# vfd.net
KiCad netlist of a schematic drawn in EAGLE
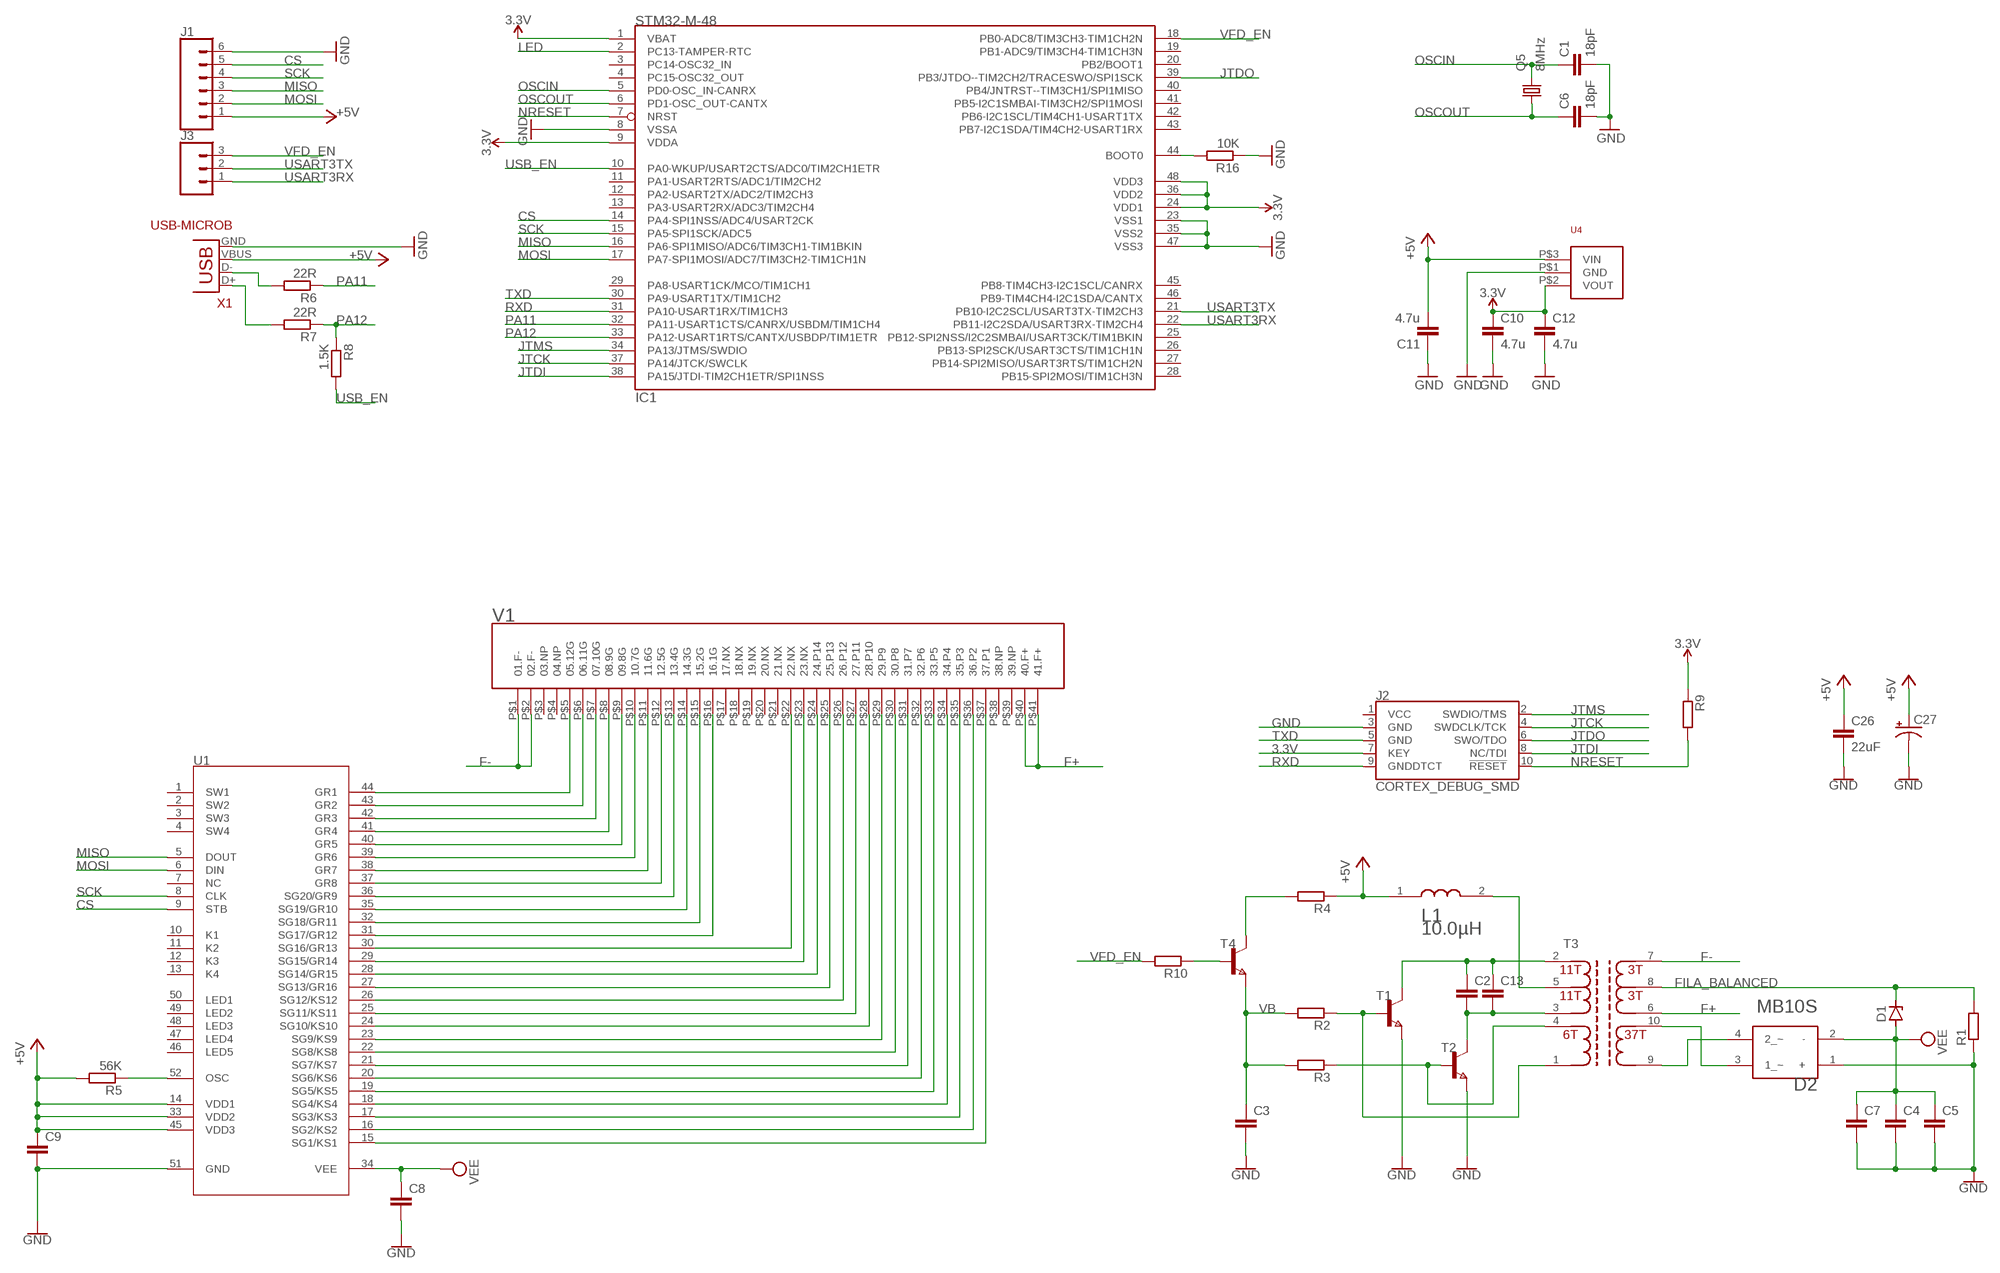
[diagram p0: schematic, sheet 1]

(export (version "E")
  (design (tool "Eeschema 10.0.6"))
  (components
    (comp (ref "C1")
      (value "18pF")
      (footprint "eagle-import:C0603")
      (libsource (lib "eagle-import") (part "resistor_348_C-EUC0603"))
    )
    (comp (ref "C2")
      (value "C-EUC1206")
      (footprint "eagle-import:C1206")
      (libsource (lib "eagle-import") (part "C-EUC1206"))
    )
    (comp (ref "C3")
      (value "C-EUC0805")
      (footprint "eagle-import:C0805")
      (libsource (lib "eagle-import") (part "C-EUC0805"))
    )
    (comp (ref "C4")
      (value "C-EUC0805")
      (footprint "eagle-import:C0805")
      (libsource (lib "eagle-import") (part "C-EUC0805"))
    )
    (comp (ref "C5")
      (value "C-EUC0805")
      (footprint "eagle-import:C0805")
      (libsource (lib "eagle-import") (part "C-EUC0805"))
    )
    (comp (ref "C6")
      (value "18pF")
      (footprint "eagle-import:C0603")
      (libsource (lib "eagle-import") (part "resistor_348_C-EUC0603"))
    )
    (comp (ref "C7")
      (value "C-EUC0805")
      (footprint "eagle-import:C0805")
      (libsource (lib "eagle-import") (part "C-EUC0805"))
    )
    (comp (ref "C8")
      (value "C-EUC0805")
      (footprint "eagle-import:C0805")
      (libsource (lib "eagle-import") (part "C-EUC0805"))
    )
    (comp (ref "C9")
      (value "C-EUC0805")
      (footprint "eagle-import:C0805")
      (libsource (lib "eagle-import") (part "C-EUC0805"))
    )
    (comp (ref "C10")
      (value "4.7u")
      (footprint "eagle-import:0805")
      (libsource (lib "eagle-import") (part "CAP0805"))
    )
    (comp (ref "C11")
      (value "4.7u")
      (footprint "eagle-import:0805")
      (libsource (lib "eagle-import") (part "CAP0805"))
    )
    (comp (ref "C12")
      (value "4.7u")
      (footprint "eagle-import:0805")
      (libsource (lib "eagle-import") (part "CAP0805"))
    )
    (comp (ref "C13")
      (value "C-EUC1206")
      (footprint "eagle-import:C1206")
      (libsource (lib "eagle-import") (part "C-EUC1206"))
    )
    (comp (ref "C26")
      (value "22uF")
      (footprint "eagle-import:C1206")
      (libsource (lib "eagle-import") (part "resistor_C-EUC1206"))
    )
    (comp (ref "C27")
      (value "CPOL-US153CLV-0807")
      (footprint "eagle-import:153CLV-0807")
      (libsource (lib "eagle-import") (part "CPOL-US153CLV-0807"))
    )
    (comp (ref "D1")
      (value "ZENER-DIODESOD80C")
      (footprint "eagle-import:SOD80C")
      (libsource (lib "eagle-import") (part "ZENER-DIODESOD80C"))
    )
    (comp (ref "D2")
      (value "ON_SEMI_MB10SON_SEMI_MB10S_0_0")
      (footprint "eagle-import:ON_SEMI_MB10S_0")
      (fields
        (field (name "DIGIKEY_PART_NUMBER") "MB10SCT-ND")
        (field (name "MF") "ON Semi")
        (field (name "MOUSER_PART_NUMBER") "512-MB10S")
      )
      (libsource (lib "eagle-import") (part "ON_SEMI_MB10SON_SEMI_MB10S_0_0"))
    )
    (comp (ref "IC1")
      (value "STM32-M-48")
      (footprint "eagle-import:LQFP48")
      (libsource (lib "eagle-import") (part "STM32-M-48"))
    )
    (comp (ref "J1")
      (value "CONN_06NO_SILK_FEMALE_PTH")
      (footprint "eagle-import:1X06_NO_SILK")
      (libsource (lib "eagle-import") (part "CONN_06NO_SILK_FEMALE_PTH"))
    )
    (comp (ref "J2")
      (value "CORTEX_DEBUG_SMD")
      (footprint "eagle-import:SAMTECH_FTSH-105-01")
      (libsource (lib "eagle-import") (part "CORTEX_DEBUG_SMD"))
    )
    (comp (ref "J3")
      (value "CONN_031X03_NO_SILK")
      (footprint "eagle-import:1X03_NO_SILK")
      (libsource (lib "eagle-import") (part "CONN_031X03_NO_SILK"))
    )
    (comp (ref "L1")
      (value "TDK_SLF7045T-100M1R3-PF")
      (footprint "eagle-import:ASWPA8050")
      (libsource (lib "eagle-import") (part "TDK_SLF7045T-100M1R3-PF"))
    )
    (comp (ref "Q5")
      (value "8MHz")
      (footprint "eagle-import:3.2X2.5_KX-7")
      (libsource (lib "eagle-import") (part "KX-7"))
    )
    (comp (ref "R1")
      (value "R-EU_R0603")
      (footprint "eagle-import:R0603")
      (libsource (lib "eagle-import") (part "R-EU_R0603"))
    )
    (comp (ref "R2")
      (value "R-EU_R0603")
      (footprint "eagle-import:R0603")
      (libsource (lib "eagle-import") (part "R-EU_R0603"))
    )
    (comp (ref "R3")
      (value "R-EU_R0603")
      (footprint "eagle-import:R0603")
      (libsource (lib "eagle-import") (part "R-EU_R0603"))
    )
    (comp (ref "R4")
      (value "R-EU_R0603")
      (footprint "eagle-import:R0603")
      (libsource (lib "eagle-import") (part "R-EU_R0603"))
    )
    (comp (ref "R5")
      (value "56K")
      (footprint "eagle-import:R0603")
      (libsource (lib "eagle-import") (part "R-EU_R0603"))
    )
    (comp (ref "R6")
      (value "22R")
      (footprint "eagle-import:R0603")
      (libsource (lib "eagle-import") (part "resistor_348_R-EU_R0603"))
    )
    (comp (ref "R7")
      (value "22R")
      (footprint "eagle-import:R0603")
      (libsource (lib "eagle-import") (part "resistor_348_R-EU_R0603"))
    )
    (comp (ref "R8")
      (value "1.5K")
      (footprint "eagle-import:R0603")
      (libsource (lib "eagle-import") (part "resistor_348_R-EU_R0603"))
    )
    (comp (ref "R9")
      (value "R-EU_R0603")
      (footprint "eagle-import:R0603")
      (libsource (lib "eagle-import") (part "R-EU_R0603"))
    )
    (comp (ref "R10")
      (value "R-EU_R0603")
      (footprint "eagle-import:R0603")
      (libsource (lib "eagle-import") (part "R-EU_R0603"))
    )
    (comp (ref "R16")
      (value "10K")
      (footprint "eagle-import:R0603")
      (libsource (lib "eagle-import") (part "resistor_348_R-EU_R0603"))
    )
    (comp (ref "T1")
      (value "NPNSOT23")
      (footprint "eagle-import:SOT-23")
      (fields (field (name "MPN") "DSS20201L-7"))
      (libsource (lib "eagle-import") (part "NPNSOT23"))
    )
    (comp (ref "T2")
      (value "NPNSOT23")
      (footprint "eagle-import:SOT-23")
      (fields (field (name "MPN") "DSS20201L-7"))
      (libsource (lib "eagle-import") (part "NPNSOT23"))
    )
    (comp (ref "T3")
      (value "TRANS_VFD_ER10P5")
      (footprint "eagle-import:ER10P5")
      (libsource (lib "eagle-import") (part "TRANS_VFD_ER10P5"))
    )
    (comp (ref "T4")
      (value "NPNSOT23")
      (footprint "eagle-import:SOT-23")
      (fields (field (name "MPN") "DSS20201L-7"))
      (libsource (lib "eagle-import") (part "NPNSOT23"))
    )
    (comp (ref "U1")
      (value "PT6311B")
      (footprint "eagle-import:QFP52_SOT379-1")
      (libsource (lib "eagle-import") (part "PT6311B"))
    )
    (comp (ref "U4")
      (value "MCP1703SOT-3.3V")
      (footprint "eagle-import:SOT-23A")
      (libsource (lib "eagle-import") (part "MCP1703SOT"))
    )
    (comp (ref "V1")
      (value "VFD_12SS62")
      (footprint "eagle-import:12SS62")
      (libsource (lib "eagle-import") (part "VFD_12SS62"))
    )
    (comp (ref "X1")
      (value "USB-MICROB")
      (footprint "eagle-import:USB-MICROB")
      (libsource (lib "eagle-import") (part "USB-MICROB"))
    )
  )
  (nets
    (net (code "1") (name "+5V") (class "Default")
      (node (ref "C11") (pin "2") (pinfunction "2_2") (pintype "passive"))
      (node (ref "C26") (pin "1") (pinfunction "1_1") (pintype "passive"))
      (node (ref "C27") (pin "+") (pinfunction "+_+") (pintype "passive"))
      (node (ref "C9") (pin "1") (pinfunction "1_1") (pintype "passive"))
      (node (ref "J1") (pin "1") (pinfunction "1_1") (pintype "passive"))
      (node (ref "L1") (pin "1") (pinfunction "1_1") (pintype "bidirectional"))
      (node (ref "R4") (pin "1") (pinfunction "1_1") (pintype "passive"))
      (node (ref "R5") (pin "2") (pinfunction "2_2") (pintype "passive"))
      (node (ref "U1") (pin "14") (pinfunction "VDD1_14") (pintype "bidirectional"))
      (node (ref "U1") (pin "33") (pinfunction "VDD2_33") (pintype "bidirectional"))
      (node (ref "U1") (pin "45") (pinfunction "VDD3_45") (pintype "bidirectional"))
      (node (ref "U4") (pin "P$3") (pinfunction "VIN_P$3") (pintype "bidirectional"))
      (node (ref "X1") (pin "VBUS") (pinfunction "VBUS_VBUS") (pintype "bidirectional"))
    )
    (net (code "2") (name "/CS") (class "Default")
      (node (ref "IC1") (pin "14") (pinfunction "PA4-SPI1NSS/ADC4/USART2CK_14") (pintype "bidirectional"))
      (node (ref "J1") (pin "5") (pinfunction "5_5") (pintype "passive"))
      (node (ref "U1") (pin "9") (pinfunction "STB_9") (pintype "bidirectional"))
    )
    (net (code "3") (name "/F+") (class "Default")
      (node (ref "T3") (pin "6") (pinfunction "6_6") (pintype "bidirectional"))
      (node (ref "V1") (pin "P$40") (pinfunction "40.F+_P$40") (pintype "bidirectional"))
      (node (ref "V1") (pin "P$41") (pinfunction "41.F+_P$41") (pintype "bidirectional"))
    )
    (net (code "4") (name "/F-") (class "Default")
      (node (ref "T3") (pin "7") (pinfunction "7_7") (pintype "bidirectional"))
      (node (ref "V1") (pin "P$1") (pinfunction "01.F-_P$1") (pintype "bidirectional"))
      (node (ref "V1") (pin "P$2") (pinfunction "02.F-_P$2") (pintype "bidirectional"))
    )
    (net (code "5") (name "/FILA_BALANCED") (class "Default")
      (node (ref "D1") (pin "C") (pinfunction "C_C") (pintype "passive"))
      (node (ref "R1") (pin "2") (pinfunction "2_2") (pintype "passive"))
      (node (ref "T3") (pin "8") (pinfunction "8_8") (pintype "bidirectional"))
    )
    (net (code "6") (name "/JTCK") (class "Default")
      (node (ref "IC1") (pin "37") (pinfunction "PA14/JTCK/SWCLK_37") (pintype "bidirectional"))
      (node (ref "J2") (pin "4") (pinfunction "SWDCLK/TCK_4") (pintype "bidirectional"))
    )
    (net (code "7") (name "/JTDI") (class "Default")
      (node (ref "IC1") (pin "38") (pinfunction "PA15/JTDI-TIM2CH1ETR/SPI1NSS_38") (pintype "bidirectional"))
      (node (ref "J2") (pin "8") (pinfunction "NC/TDI_8") (pintype "bidirectional"))
    )
    (net (code "8") (name "/JTDO") (class "Default")
      (node (ref "IC1") (pin "39") (pinfunction "PB3/JTDO--TIM2CH2/TRACESWO/SPI1SCK_39") (pintype "bidirectional"))
      (node (ref "J2") (pin "6") (pinfunction "SWO/TDO_6") (pintype "bidirectional"))
    )
    (net (code "9") (name "/JTMS") (class "Default")
      (node (ref "IC1") (pin "34") (pinfunction "PA13/JTMS/SWDIO_34") (pintype "bidirectional"))
      (node (ref "J2") (pin "2") (pinfunction "SWDIO/TMS_2") (pintype "bidirectional"))
    )
    (net (code "10") (name "/LED") (class "Default")
      (node (ref "IC1") (pin "2") (pinfunction "PC13-TAMPER-RTC_2") (pintype "bidirectional"))
    )
    (net (code "11") (name "/MISO") (class "Default")
      (node (ref "IC1") (pin "16") (pinfunction "PA6-SPI1MISO/ADC6/TIM3CH1-TIM1BKIN_16") (pintype "bidirectional"))
      (node (ref "J1") (pin "3") (pinfunction "3_3") (pintype "passive"))
      (node (ref "U1") (pin "5") (pinfunction "DOUT_5") (pintype "bidirectional"))
    )
    (net (code "12") (name "/MOSI") (class "Default")
      (node (ref "IC1") (pin "17") (pinfunction "PA7-SPI1MOSI/ADC7/TIM3CH2-TIM1CH1N_17") (pintype "bidirectional"))
      (node (ref "J1") (pin "2") (pinfunction "2_2") (pintype "passive"))
      (node (ref "U1") (pin "6") (pinfunction "DIN_6") (pintype "bidirectional"))
    )
    (net (code "13") (name "/NRESET") (class "Default")
      (node (ref "IC1") (pin "7") (pinfunction "NRST_7") (pintype "bidirectional"))
      (node (ref "J2") (pin "10") (pinfunction "~{RESET}_10") (pintype "bidirectional"))
      (node (ref "R9") (pin "2") (pinfunction "2_2") (pintype "passive"))
    )
    (net (code "14") (name "/OSCIN") (class "Default")
      (node (ref "C1") (pin "1") (pinfunction "1_1") (pintype "passive"))
      (node (ref "IC1") (pin "5") (pinfunction "PD0-OSC_IN-CANRX_5") (pintype "input"))
      (node (ref "Q5") (pin "3") (pinfunction "2_3") (pintype "passive"))
    )
    (net (code "15") (name "/OSCOUT") (class "Default")
      (node (ref "C6") (pin "1") (pinfunction "1_1") (pintype "passive"))
      (node (ref "IC1") (pin "6") (pinfunction "PD1-OSC_OUT-CANTX_6") (pintype "output"))
      (node (ref "Q5") (pin "1") (pinfunction "1_1") (pintype "passive"))
    )
    (net (code "16") (name "/PA11") (class "Default")
      (node (ref "IC1") (pin "32") (pinfunction "PA11-USART1CTS/CANRX/USBDM/TIM1CH4_32") (pintype "bidirectional"))
      (node (ref "R6") (pin "1") (pinfunction "1_1") (pintype "passive"))
    )
    (net (code "17") (name "/PA12") (class "Default")
      (node (ref "IC1") (pin "33") (pinfunction "PA12-USART1RTS/CANTX/USBDP/TIM1ETR_33") (pintype "bidirectional"))
      (node (ref "R7") (pin "1") (pinfunction "1_1") (pintype "passive"))
      (node (ref "R8") (pin "1") (pinfunction "1_1") (pintype "passive"))
    )
    (net (code "18") (name "/RXD") (class "Default")
      (node (ref "IC1") (pin "31") (pinfunction "PA10-USART1RX/TIM1CH3_31") (pintype "bidirectional"))
      (node (ref "J2") (pin "9") (pinfunction "GNDDTCT_9") (pintype "bidirectional"))
    )
    (net (code "19") (name "/SCK") (class "Default")
      (node (ref "IC1") (pin "15") (pinfunction "PA5-SPI1SCK/ADC5_15") (pintype "bidirectional"))
      (node (ref "J1") (pin "4") (pinfunction "4_4") (pintype "passive"))
      (node (ref "U1") (pin "8") (pinfunction "CLK_8") (pintype "bidirectional"))
    )
    (net (code "20") (name "/TXD") (class "Default")
      (node (ref "IC1") (pin "30") (pinfunction "PA9-USART1TX/TIM1CH2_30") (pintype "bidirectional"))
      (node (ref "J2") (pin "5") (pinfunction "GND_5") (pintype "bidirectional"))
    )
    (net (code "21") (name "/USART3RX") (class "Default")
      (node (ref "IC1") (pin "22") (pinfunction "PB11-I2C2SDA/USART3RX-TIM2CH4_22") (pintype "bidirectional"))
      (node (ref "J3") (pin "1") (pinfunction "1_1") (pintype "passive"))
    )
    (net (code "22") (name "/USART3TX") (class "Default")
      (node (ref "IC1") (pin "21") (pinfunction "PB10-I2C2SCL/USART3TX-TIM2CH3_21") (pintype "bidirectional"))
      (node (ref "J3") (pin "2") (pinfunction "2_2") (pintype "passive"))
    )
    (net (code "23") (name "/USB_EN") (class "Default")
      (node (ref "IC1") (pin "10") (pinfunction "PA0-WKUP/USART2CTS/ADC0/TIM2CH1ETR_10") (pintype "bidirectional"))
      (node (ref "R8") (pin "2") (pinfunction "2_2") (pintype "passive"))
    )
    (net (code "24") (name "/VB") (class "Default")
      (node (ref "C3") (pin "1") (pinfunction "1_1") (pintype "passive"))
      (node (ref "R2") (pin "2") (pinfunction "2_2") (pintype "passive"))
      (node (ref "R3") (pin "2") (pinfunction "2_2") (pintype "passive"))
      (node (ref "T4") (pin "2") (pinfunction "E_2") (pintype "passive"))
    )
    (net (code "25") (name "/VFD_EN") (class "Default")
      (node (ref "IC1") (pin "18") (pinfunction "PB0-ADC8/TIM3CH3-TIM1CH2N_18") (pintype "bidirectional"))
      (node (ref "J3") (pin "3") (pinfunction "3_3") (pintype "passive"))
      (node (ref "R10") (pin "2") (pinfunction "2_2") (pintype "passive"))
    )
    (net (code "26") (name "3.3V") (class "Default")
      (node (ref "C10") (pin "1") (pinfunction "1_1") (pintype "passive"))
      (node (ref "C12") (pin "1") (pinfunction "1_1") (pintype "passive"))
      (node (ref "IC1") (pin "1") (pinfunction "VBAT_1") (pintype "power_in"))
      (node (ref "IC1") (pin "24") (pinfunction "VDD1_24") (pintype "power_in"))
      (node (ref "IC1") (pin "36") (pinfunction "VDD2_36") (pintype "power_in"))
      (node (ref "IC1") (pin "48") (pinfunction "VDD3_48") (pintype "power_in"))
      (node (ref "IC1") (pin "9") (pinfunction "VDDA_9") (pintype "power_in"))
      (node (ref "J2") (pin "7") (pinfunction "KEY_7") (pintype "bidirectional"))
      (node (ref "R9") (pin "1") (pinfunction "1_1") (pintype "passive"))
      (node (ref "U4") (pin "P$2") (pinfunction "VOUT_P$2") (pintype "bidirectional"))
    )
    (net (code "27") (name "GND") (class "Default")
      (node (ref "C1") (pin "2") (pinfunction "2_2") (pintype "passive"))
      (node (ref "C10") (pin "2") (pinfunction "2_2") (pintype "passive"))
      (node (ref "C11") (pin "1") (pinfunction "1_1") (pintype "passive"))
      (node (ref "C12") (pin "2") (pinfunction "2_2") (pintype "passive"))
      (node (ref "C26") (pin "2") (pinfunction "2_2") (pintype "passive"))
      (node (ref "C27") (pin "-") (pinfunction "-_-") (pintype "passive"))
      (node (ref "C3") (pin "2") (pinfunction "2_2") (pintype "passive"))
      (node (ref "C4") (pin "2") (pinfunction "2_2") (pintype "passive"))
      (node (ref "C5") (pin "2") (pinfunction "2_2") (pintype "passive"))
      (node (ref "C6") (pin "2") (pinfunction "2_2") (pintype "passive"))
      (node (ref "C7") (pin "2") (pinfunction "2_2") (pintype "passive"))
      (node (ref "C8") (pin "2") (pinfunction "2_2") (pintype "passive"))
      (node (ref "C9") (pin "2") (pinfunction "2_2") (pintype "passive"))
      (node (ref "D2") (pin "1") (pinfunction "+_1") (pintype "passive"))
      (node (ref "IC1") (pin "23") (pinfunction "VSS1_23") (pintype "power_in"))
      (node (ref "IC1") (pin "35") (pinfunction "VSS2_35") (pintype "power_in"))
      (node (ref "IC1") (pin "47") (pinfunction "VSS3_47") (pintype "power_in"))
      (node (ref "IC1") (pin "8") (pinfunction "VSSA_8") (pintype "power_in"))
      (node (ref "J1") (pin "6") (pinfunction "6_6") (pintype "passive"))
      (node (ref "J2") (pin "3") (pinfunction "GND_3") (pintype "bidirectional"))
      (node (ref "R1") (pin "1") (pinfunction "1_1") (pintype "passive"))
      (node (ref "R16") (pin "1") (pinfunction "1_1") (pintype "passive"))
      (node (ref "T1") (pin "2") (pinfunction "E_2") (pintype "passive"))
      (node (ref "T2") (pin "2") (pinfunction "E_2") (pintype "passive"))
      (node (ref "U1") (pin "51") (pinfunction "GND_51") (pintype "bidirectional"))
      (node (ref "U4") (pin "P$1") (pinfunction "GND_P$1") (pintype "bidirectional"))
      (node (ref "X1") (pin "GND") (pinfunction "GND_GND") (pintype "bidirectional"))
    )
    (net (code "28") (name "Net-(D2-1_~{})") (class "Default")
      (node (ref "D2") (pin "3") (pinfunction "1_~{}_3") (pintype "passive"))
      (node (ref "T3") (pin "10") (pinfunction "10_10") (pintype "bidirectional"))
    )
    (net (code "29") (name "Net-(D2-2_~{})") (class "Default")
      (node (ref "D2") (pin "4") (pinfunction "2_~{}_4") (pintype "passive"))
      (node (ref "T3") (pin "9") (pinfunction "9_9") (pintype "bidirectional"))
    )
    (net (code "30") (name "Net-(IC1-BOOT0)") (class "Default")
      (node (ref "IC1") (pin "44") (pinfunction "BOOT0_44") (pintype "input"))
      (node (ref "R16") (pin "2") (pinfunction "2_2") (pintype "passive"))
    )
    (net (code "31") (name "Net-(L1-Pad2)") (class "Default")
      (node (ref "L1") (pin "2") (pinfunction "2_2") (pintype "bidirectional"))
      (node (ref "T3") (pin "5") (pinfunction "5_5") (pintype "bidirectional"))
    )
    (net (code "32") (name "Net-(R6-Pad2)") (class "Default")
      (node (ref "R6") (pin "2") (pinfunction "2_2") (pintype "passive"))
      (node (ref "X1") (pin "D-") (pinfunction "D-_D-") (pintype "bidirectional"))
    )
    (net (code "33") (name "Net-(R7-Pad2)") (class "Default")
      (node (ref "R7") (pin "2") (pinfunction "2_2") (pintype "passive"))
      (node (ref "X1") (pin "D+") (pinfunction "D+_D+") (pintype "bidirectional"))
    )
    (net (code "34") (name "Net-(T1-B)") (class "Default")
      (node (ref "R2") (pin "1") (pinfunction "1_1") (pintype "passive"))
      (node (ref "T1") (pin "3") (pinfunction "B_3") (pintype "passive"))
      (node (ref "T3") (pin "1") (pinfunction "1_1") (pintype "bidirectional"))
    )
    (net (code "35") (name "Net-(T1-C)") (class "Default")
      (node (ref "C13") (pin "1") (pinfunction "1_1") (pintype "passive"))
      (node (ref "C2") (pin "1") (pinfunction "1_1") (pintype "passive"))
      (node (ref "T1") (pin "1") (pinfunction "C_1") (pintype "passive"))
      (node (ref "T3") (pin "2") (pinfunction "2_2") (pintype "bidirectional"))
    )
    (net (code "36") (name "Net-(T2-B)") (class "Default")
      (node (ref "R3") (pin "1") (pinfunction "1_1") (pintype "passive"))
      (node (ref "T2") (pin "3") (pinfunction "B_3") (pintype "passive"))
      (node (ref "T3") (pin "4") (pinfunction "4_4") (pintype "bidirectional"))
    )
    (net (code "37") (name "Net-(T2-C)") (class "Default")
      (node (ref "C13") (pin "2") (pinfunction "2_2") (pintype "passive"))
      (node (ref "C2") (pin "2") (pinfunction "2_2") (pintype "passive"))
      (node (ref "T2") (pin "1") (pinfunction "C_1") (pintype "passive"))
      (node (ref "T3") (pin "3") (pinfunction "3_3") (pintype "bidirectional"))
    )
    (net (code "38") (name "Net-(T4-B)") (class "Default")
      (node (ref "R10") (pin "1") (pinfunction "1_1") (pintype "passive"))
      (node (ref "T4") (pin "3") (pinfunction "B_3") (pintype "passive"))
    )
    (net (code "39") (name "Net-(T4-C)") (class "Default")
      (node (ref "R4") (pin "2") (pinfunction "2_2") (pintype "passive"))
      (node (ref "T4") (pin "1") (pinfunction "C_1") (pintype "passive"))
    )
    (net (code "40") (name "Net-(U1-GR1)") (class "Default")
      (node (ref "U1") (pin "44") (pinfunction "GR1_44") (pintype "bidirectional"))
      (node (ref "V1") (pin "P$5") (pinfunction "05.12G_P$5") (pintype "bidirectional"))
    )
    (net (code "41") (name "Net-(U1-GR2)") (class "Default")
      (node (ref "U1") (pin "43") (pinfunction "GR2_43") (pintype "bidirectional"))
      (node (ref "V1") (pin "P$6") (pinfunction "06.11G_P$6") (pintype "bidirectional"))
    )
    (net (code "42") (name "Net-(U1-GR3)") (class "Default")
      (node (ref "U1") (pin "42") (pinfunction "GR3_42") (pintype "bidirectional"))
      (node (ref "V1") (pin "P$7") (pinfunction "07.10G_P$7") (pintype "bidirectional"))
    )
    (net (code "43") (name "Net-(U1-GR4)") (class "Default")
      (node (ref "U1") (pin "41") (pinfunction "GR4_41") (pintype "bidirectional"))
      (node (ref "V1") (pin "P$8") (pinfunction "08.9G_P$8") (pintype "bidirectional"))
    )
    (net (code "44") (name "Net-(U1-GR5)") (class "Default")
      (node (ref "U1") (pin "40") (pinfunction "GR5_40") (pintype "bidirectional"))
      (node (ref "V1") (pin "P$9") (pinfunction "09.8G_P$9") (pintype "bidirectional"))
    )
    (net (code "45") (name "Net-(U1-GR6)") (class "Default")
      (node (ref "U1") (pin "39") (pinfunction "GR6_39") (pintype "bidirectional"))
      (node (ref "V1") (pin "P$10") (pinfunction "10.7G_P$10") (pintype "bidirectional"))
    )
    (net (code "46") (name "Net-(U1-GR7)") (class "Default")
      (node (ref "U1") (pin "38") (pinfunction "GR7_38") (pintype "bidirectional"))
      (node (ref "V1") (pin "P$11") (pinfunction "11.6G_P$11") (pintype "bidirectional"))
    )
    (net (code "47") (name "Net-(U1-GR8)") (class "Default")
      (node (ref "U1") (pin "37") (pinfunction "GR8_37") (pintype "bidirectional"))
      (node (ref "V1") (pin "P$12") (pinfunction "12.5G_P$12") (pintype "bidirectional"))
    )
    (net (code "48") (name "Net-(U1-OSC)") (class "Default")
      (node (ref "R5") (pin "1") (pinfunction "1_1") (pintype "passive"))
      (node (ref "U1") (pin "52") (pinfunction "OSC_52") (pintype "bidirectional"))
    )
    (net (code "49") (name "Net-(U1-SG1{slash}KS1)") (class "Default")
      (node (ref "U1") (pin "15") (pinfunction "SG1/KS1_15") (pintype "bidirectional"))
      (node (ref "V1") (pin "P$37") (pinfunction "37.P1_P$37") (pintype "bidirectional"))
    )
    (net (code "50") (name "Net-(U1-SG2{slash}KS2)") (class "Default")
      (node (ref "U1") (pin "16") (pinfunction "SG2/KS2_16") (pintype "bidirectional"))
      (node (ref "V1") (pin "P$36") (pinfunction "36.P2_P$36") (pintype "bidirectional"))
    )
    (net (code "51") (name "Net-(U1-SG3{slash}KS3)") (class "Default")
      (node (ref "U1") (pin "17") (pinfunction "SG3/KS3_17") (pintype "bidirectional"))
      (node (ref "V1") (pin "P$35") (pinfunction "35.P3_P$35") (pintype "bidirectional"))
    )
    (net (code "52") (name "Net-(U1-SG4{slash}KS4)") (class "Default")
      (node (ref "U1") (pin "18") (pinfunction "SG4/KS4_18") (pintype "bidirectional"))
      (node (ref "V1") (pin "P$34") (pinfunction "34.P4_P$34") (pintype "bidirectional"))
    )
    (net (code "53") (name "Net-(U1-SG5{slash}KS5)") (class "Default")
      (node (ref "U1") (pin "19") (pinfunction "SG5/KS5_19") (pintype "bidirectional"))
      (node (ref "V1") (pin "P$33") (pinfunction "33.P5_P$33") (pintype "bidirectional"))
    )
    (net (code "54") (name "Net-(U1-SG6{slash}KS6)") (class "Default")
      (node (ref "U1") (pin "20") (pinfunction "SG6/KS6_20") (pintype "bidirectional"))
      (node (ref "V1") (pin "P$32") (pinfunction "32.P6_P$32") (pintype "bidirectional"))
    )
    (net (code "55") (name "Net-(U1-SG7{slash}KS7)") (class "Default")
      (node (ref "U1") (pin "21") (pinfunction "SG7/KS7_21") (pintype "bidirectional"))
      (node (ref "V1") (pin "P$31") (pinfunction "31.P7_P$31") (pintype "bidirectional"))
    )
    (net (code "56") (name "Net-(U1-SG8{slash}KS8)") (class "Default")
      (node (ref "U1") (pin "22") (pinfunction "SG8/KS8_22") (pintype "bidirectional"))
      (node (ref "V1") (pin "P$30") (pinfunction "30.P8_P$30") (pintype "bidirectional"))
    )
    (net (code "57") (name "Net-(U1-SG9{slash}KS9)") (class "Default")
      (node (ref "U1") (pin "23") (pinfunction "SG9/KS9_23") (pintype "bidirectional"))
      (node (ref "V1") (pin "P$29") (pinfunction "29.P9_P$29") (pintype "bidirectional"))
    )
    (net (code "58") (name "Net-(U1-SG10{slash}KS10)") (class "Default")
      (node (ref "U1") (pin "24") (pinfunction "SG10/KS10_24") (pintype "bidirectional"))
      (node (ref "V1") (pin "P$28") (pinfunction "28.P10_P$28") (pintype "bidirectional"))
    )
    (net (code "59") (name "Net-(U1-SG11{slash}KS11)") (class "Default")
      (node (ref "U1") (pin "25") (pinfunction "SG11/KS11_25") (pintype "bidirectional"))
      (node (ref "V1") (pin "P$27") (pinfunction "27.P11_P$27") (pintype "bidirectional"))
    )
    (net (code "60") (name "Net-(U1-SG12{slash}KS12)") (class "Default")
      (node (ref "U1") (pin "26") (pinfunction "SG12/KS12_26") (pintype "bidirectional"))
      (node (ref "V1") (pin "P$26") (pinfunction "26.P12_P$26") (pintype "bidirectional"))
    )
    (net (code "61") (name "Net-(U1-SG13{slash}GR16)") (class "Default")
      (node (ref "U1") (pin "27") (pinfunction "SG13/GR16_27") (pintype "bidirectional"))
      (node (ref "V1") (pin "P$25") (pinfunction "25.P13_P$25") (pintype "bidirectional"))
    )
    (net (code "62") (name "Net-(U1-SG14{slash}GR15)") (class "Default")
      (node (ref "U1") (pin "28") (pinfunction "SG14/GR15_28") (pintype "bidirectional"))
      (node (ref "V1") (pin "P$24") (pinfunction "24.P14_P$24") (pintype "bidirectional"))
    )
    (net (code "63") (name "Net-(U1-SG15{slash}GR14)") (class "Default")
      (node (ref "U1") (pin "29") (pinfunction "SG15/GR14_29") (pintype "bidirectional"))
      (node (ref "V1") (pin "P$23") (pinfunction "23.NX_P$23") (pintype "bidirectional"))
    )
    (net (code "64") (name "Net-(U1-SG16{slash}GR13)") (class "Default")
      (node (ref "U1") (pin "30") (pinfunction "SG16/GR13_30") (pintype "bidirectional"))
      (node (ref "V1") (pin "P$22") (pinfunction "22.NX_P$22") (pintype "bidirectional"))
    )
    (net (code "65") (name "Net-(U1-SG17{slash}GR12)") (class "Default")
      (node (ref "U1") (pin "31") (pinfunction "SG17/GR12_31") (pintype "bidirectional"))
      (node (ref "V1") (pin "P$16") (pinfunction "16.1G_P$16") (pintype "bidirectional"))
    )
    (net (code "66") (name "Net-(U1-SG18{slash}GR11)") (class "Default")
      (node (ref "U1") (pin "32") (pinfunction "SG18/GR11_32") (pintype "bidirectional"))
      (node (ref "V1") (pin "P$15") (pinfunction "15.2G_P$15") (pintype "bidirectional"))
    )
    (net (code "67") (name "Net-(U1-SG19{slash}GR10)") (class "Default")
      (node (ref "U1") (pin "35") (pinfunction "SG19/GR10_35") (pintype "bidirectional"))
      (node (ref "V1") (pin "P$14") (pinfunction "14.3G_P$14") (pintype "bidirectional"))
    )
    (net (code "68") (name "Net-(U1-SG20{slash}GR9)") (class "Default")
      (node (ref "U1") (pin "36") (pinfunction "SG20/GR9_36") (pintype "bidirectional"))
      (node (ref "V1") (pin "P$13") (pinfunction "13.4G_P$13") (pintype "bidirectional"))
    )
    (net (code "69") (name "VEE") (class "Default")
      (node (ref "C4") (pin "1") (pinfunction "1_1") (pintype "passive"))
      (node (ref "C5") (pin "1") (pinfunction "1_1") (pintype "passive"))
      (node (ref "C7") (pin "1") (pinfunction "1_1") (pintype "passive"))
      (node (ref "C8") (pin "1") (pinfunction "1_1") (pintype "passive"))
      (node (ref "D1") (pin "A") (pinfunction "A_A") (pintype "passive"))
      (node (ref "D2") (pin "2") (pinfunction "-_2") (pintype "passive"))
      (node (ref "U1") (pin "34") (pinfunction "VEE_34") (pintype "bidirectional"))
    )
    (net (code "70") (name "unconnected-(IC1-PA1-USART2RTS{slash}ADC1{slash}TIM2CH2-Pad11)") (class "Default")
      (node (ref "IC1") (pin "11") (pinfunction "PA1-USART2RTS/ADC1/TIM2CH2_11") (pintype "bidirectional"))
    )
    (net (code "71") (name "unconnected-(IC1-PA2-USART2TX{slash}ADC2{slash}TIM2CH3-Pad12)") (class "Default")
      (node (ref "IC1") (pin "12") (pinfunction "PA2-USART2TX/ADC2/TIM2CH3_12") (pintype "bidirectional"))
    )
    (net (code "72") (name "unconnected-(IC1-PA3-USART2RX{slash}ADC3{slash}TIM2CH4-Pad13)") (class "Default")
      (node (ref "IC1") (pin "13") (pinfunction "PA3-USART2RX/ADC3/TIM2CH4_13") (pintype "bidirectional"))
    )
    (net (code "73") (name "unconnected-(IC1-PA8-USART1CK{slash}MCO{slash}TIM1CH1-Pad29)") (class "Default")
      (node (ref "IC1") (pin "29") (pinfunction "PA8-USART1CK/MCO/TIM1CH1_29") (pintype "bidirectional"))
    )
    (net (code "74") (name "unconnected-(IC1-PB1-ADC9{slash}TIM3CH4-TIM1CH3N-Pad19)") (class "Default")
      (node (ref "IC1") (pin "19") (pinfunction "PB1-ADC9/TIM3CH4-TIM1CH3N_19") (pintype "bidirectional"))
    )
    (net (code "75") (name "unconnected-(IC1-PB2{slash}BOOT1-Pad20)") (class "Default")
      (node (ref "IC1") (pin "20") (pinfunction "PB2/BOOT1_20") (pintype "bidirectional"))
    )
    (net (code "76") (name "unconnected-(IC1-PB4{slash}JNTRST--TIM3CH1{slash}SPI1MISO-Pad40)") (class "Default")
      (node (ref "IC1") (pin "40") (pinfunction "PB4/JNTRST--TIM3CH1/SPI1MISO_40") (pintype "bidirectional"))
    )
    (net (code "77") (name "unconnected-(IC1-PB5-I2C1SMBAI-TIM3CH2{slash}SPI1MOSI-Pad41)") (class "Default")
      (node (ref "IC1") (pin "41") (pinfunction "PB5-I2C1SMBAI-TIM3CH2/SPI1MOSI_41") (pintype "bidirectional"))
    )
    (net (code "78") (name "unconnected-(IC1-PB6-I2C1SCL{slash}TIM4CH1-USART1TX-Pad42)") (class "Default")
      (node (ref "IC1") (pin "42") (pinfunction "PB6-I2C1SCL/TIM4CH1-USART1TX_42") (pintype "bidirectional"))
    )
    (net (code "79") (name "unconnected-(IC1-PB7-I2C1SDA{slash}TIM4CH2-USART1RX-Pad43)") (class "Default")
      (node (ref "IC1") (pin "43") (pinfunction "PB7-I2C1SDA/TIM4CH2-USART1RX_43") (pintype "bidirectional"))
    )
    (net (code "80") (name "unconnected-(IC1-PB8-TIM4CH3-I2C1SCL{slash}CANRX-Pad45)") (class "Default")
      (node (ref "IC1") (pin "45") (pinfunction "PB8-TIM4CH3-I2C1SCL/CANRX_45") (pintype "bidirectional"))
    )
    (net (code "81") (name "unconnected-(IC1-PB9-TIM4CH4-I2C1SDA{slash}CANTX-Pad46)") (class "Default")
      (node (ref "IC1") (pin "46") (pinfunction "PB9-TIM4CH4-I2C1SDA/CANTX_46") (pintype "bidirectional"))
    )
    (net (code "82") (name "unconnected-(IC1-PB12-SPI2NSS{slash}I2C2SMBAI{slash}USART3CK{slash}TIM1BKIN-Pad25)") (class "Default")
      (node (ref "IC1") (pin "25") (pinfunction "PB12-SPI2NSS/I2C2SMBAI/USART3CK/TIM1BKIN_25") (pintype "bidirectional"))
    )
    (net (code "83") (name "unconnected-(IC1-PB13-SPI2SCK{slash}USART3CTS{slash}TIM1CH1N-Pad26)") (class "Default")
      (node (ref "IC1") (pin "26") (pinfunction "PB13-SPI2SCK/USART3CTS/TIM1CH1N_26") (pintype "bidirectional"))
    )
    (net (code "84") (name "unconnected-(IC1-PB14-SPI2MISO{slash}USART3RTS{slash}TIM1CH2N-Pad27)") (class "Default")
      (node (ref "IC1") (pin "27") (pinfunction "PB14-SPI2MISO/USART3RTS/TIM1CH2N_27") (pintype "bidirectional"))
    )
    (net (code "85") (name "unconnected-(IC1-PB15-SPI2MOSI{slash}TIM1CH3N-Pad28)") (class "Default")
      (node (ref "IC1") (pin "28") (pinfunction "PB15-SPI2MOSI/TIM1CH3N_28") (pintype "bidirectional"))
    )
    (net (code "86") (name "unconnected-(IC1-PC14-OSC32_IN-Pad3)") (class "Default")
      (node (ref "IC1") (pin "3") (pinfunction "PC14-OSC32_IN_3") (pintype "bidirectional"))
    )
    (net (code "87") (name "unconnected-(IC1-PC15-OSC32_OUT-Pad4)") (class "Default")
      (node (ref "IC1") (pin "4") (pinfunction "PC15-OSC32_OUT_4") (pintype "bidirectional"))
    )
    (net (code "88") (name "unconnected-(J2-VCC-Pad1)") (class "Default")
      (node (ref "J2") (pin "1") (pinfunction "VCC_1") (pintype "bidirectional"))
    )
    (net (code "89") (name "unconnected-(U1-K1-Pad10)") (class "Default")
      (node (ref "U1") (pin "10") (pinfunction "K1_10") (pintype "bidirectional"))
    )
    (net (code "90") (name "unconnected-(U1-K2-Pad11)") (class "Default")
      (node (ref "U1") (pin "11") (pinfunction "K2_11") (pintype "bidirectional"))
    )
    (net (code "91") (name "unconnected-(U1-K3-Pad12)") (class "Default")
      (node (ref "U1") (pin "12") (pinfunction "K3_12") (pintype "bidirectional"))
    )
    (net (code "92") (name "unconnected-(U1-K4-Pad13)") (class "Default")
      (node (ref "U1") (pin "13") (pinfunction "K4_13") (pintype "bidirectional"))
    )
    (net (code "93") (name "unconnected-(U1-LED1-Pad50)") (class "Default")
      (node (ref "U1") (pin "50") (pinfunction "LED1_50") (pintype "bidirectional"))
    )
    (net (code "94") (name "unconnected-(U1-LED2-Pad49)") (class "Default")
      (node (ref "U1") (pin "49") (pinfunction "LED2_49") (pintype "bidirectional"))
    )
    (net (code "95") (name "unconnected-(U1-LED3-Pad48)") (class "Default")
      (node (ref "U1") (pin "48") (pinfunction "LED3_48") (pintype "bidirectional"))
    )
    (net (code "96") (name "unconnected-(U1-LED4-Pad47)") (class "Default")
      (node (ref "U1") (pin "47") (pinfunction "LED4_47") (pintype "bidirectional"))
    )
    (net (code "97") (name "unconnected-(U1-LED5-Pad46)") (class "Default")
      (node (ref "U1") (pin "46") (pinfunction "LED5_46") (pintype "bidirectional"))
    )
    (net (code "98") (name "unconnected-(U1-NC-Pad7)") (class "Default")
      (node (ref "U1") (pin "7") (pinfunction "NC_7") (pintype "bidirectional"))
    )
    (net (code "99") (name "unconnected-(U1-SW1-Pad1)") (class "Default")
      (node (ref "U1") (pin "1") (pinfunction "SW1_1") (pintype "bidirectional"))
    )
    (net (code "100") (name "unconnected-(U1-SW2-Pad2)") (class "Default")
      (node (ref "U1") (pin "2") (pinfunction "SW2_2") (pintype "bidirectional"))
    )
    (net (code "101") (name "unconnected-(U1-SW3-Pad3)") (class "Default")
      (node (ref "U1") (pin "3") (pinfunction "SW3_3") (pintype "bidirectional"))
    )
    (net (code "102") (name "unconnected-(U1-SW4-Pad4)") (class "Default")
      (node (ref "U1") (pin "4") (pinfunction "SW4_4") (pintype "bidirectional"))
    )
    (net (code "103") (name "unconnected-(V1-03.NP-PadP$3)") (class "Default")
      (node (ref "V1") (pin "P$3") (pinfunction "03.NP_P$3") (pintype "bidirectional"))
    )
    (net (code "104") (name "unconnected-(V1-04.NP-PadP$4)") (class "Default")
      (node (ref "V1") (pin "P$4") (pinfunction "04.NP_P$4") (pintype "bidirectional"))
    )
    (net (code "105") (name "unconnected-(V1-17.NX-PadP$17)") (class "Default")
      (node (ref "V1") (pin "P$17") (pinfunction "17.NX_P$17") (pintype "bidirectional"))
    )
    (net (code "106") (name "unconnected-(V1-18.NX-PadP$18)") (class "Default")
      (node (ref "V1") (pin "P$18") (pinfunction "18.NX_P$18") (pintype "bidirectional"))
    )
    (net (code "107") (name "unconnected-(V1-19.NX-PadP$19)") (class "Default")
      (node (ref "V1") (pin "P$19") (pinfunction "19.NX_P$19") (pintype "bidirectional"))
    )
    (net (code "108") (name "unconnected-(V1-20.NX-PadP$20)") (class "Default")
      (node (ref "V1") (pin "P$20") (pinfunction "20.NX_P$20") (pintype "bidirectional"))
    )
    (net (code "109") (name "unconnected-(V1-21.NX-PadP$21)") (class "Default")
      (node (ref "V1") (pin "P$21") (pinfunction "21.NX_P$21") (pintype "bidirectional"))
    )
    (net (code "110") (name "unconnected-(V1-38.NP-PadP$38)") (class "Default")
      (node (ref "V1") (pin "P$38") (pinfunction "38.NP_P$38") (pintype "bidirectional"))
    )
    (net (code "111") (name "unconnected-(V1-39.NP-PadP$39)") (class "Default")
      (node (ref "V1") (pin "P$39") (pinfunction "39.NP_P$39") (pintype "bidirectional"))
    )
  )
)
